# CR78-TB.net
KiCad netlist of a schematic drawn in EAGLE
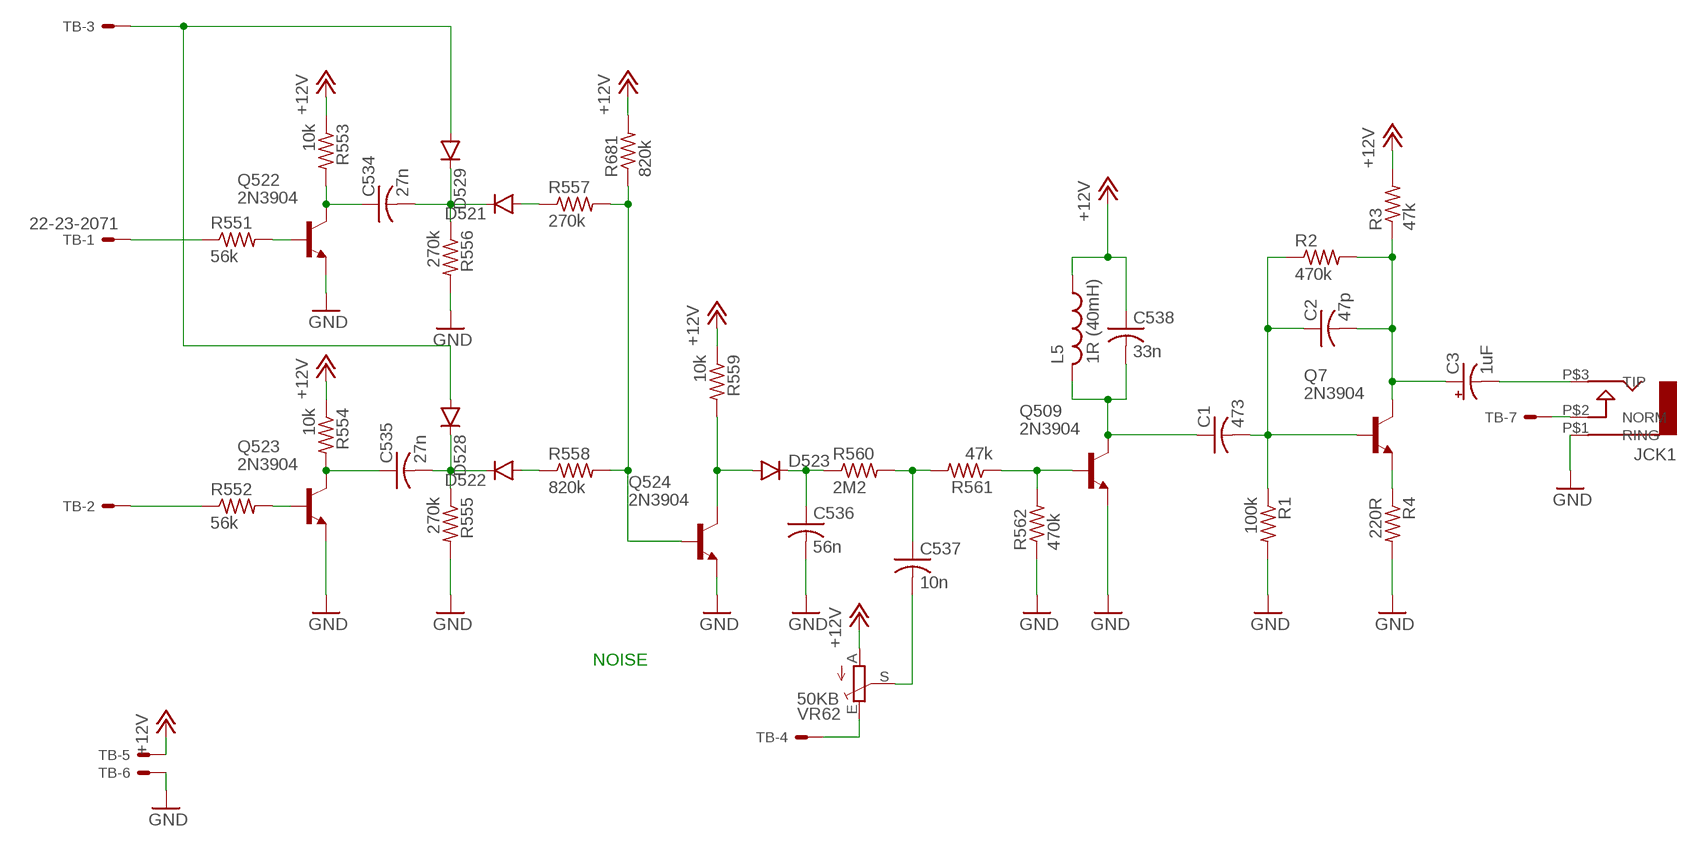
[diagram p0: schematic, sheet 1]

(export (version "E")
  (design (tool "Eeschema 10.0.6"))
  (components
    (comp (ref "C1")
      (value "473")
      (footprint "eagle-import:C050-025X075")
      (libsource (lib "eagle-import") (part "C-US050-025X075"))
    )
    (comp (ref "C2")
      (value "47p")
      (footprint "eagle-import:C050-025X075")
      (libsource (lib "eagle-import") (part "C-US050-025X075"))
    )
    (comp (ref "C3")
      (value "1uF")
      (footprint "eagle-import:B45181A")
      (libsource (lib "eagle-import") (part "CPOL-USB45181A"))
    )
    (comp (ref "C534")
      (value "27n")
      (footprint "eagle-import:C050-025X075")
      (libsource (lib "eagle-import") (part "C-US050-025X075"))
    )
    (comp (ref "C535")
      (value "27n")
      (footprint "eagle-import:C050-025X075")
      (libsource (lib "eagle-import") (part "C-US050-025X075"))
    )
    (comp (ref "C536")
      (value "56n")
      (footprint "eagle-import:C050-025X075")
      (libsource (lib "eagle-import") (part "C-US050-025X075"))
    )
    (comp (ref "C537")
      (value "10n")
      (footprint "eagle-import:C050-025X075")
      (libsource (lib "eagle-import") (part "C-US050-025X075"))
    )
    (comp (ref "C538")
      (value "33n")
      (footprint "eagle-import:C050-025X075")
      (libsource (lib "eagle-import") (part "C-US050-025X075"))
    )
    (comp (ref "D521")
      (value "DIODE1N4148")
      (footprint "eagle-import:DIODE-1N4148")
      (libsource (lib "eagle-import") (part "DIODE1N4148"))
    )
    (comp (ref "D522")
      (value "DIODE1N4148")
      (footprint "eagle-import:DIODE-1N4148")
      (libsource (lib "eagle-import") (part "DIODE1N4148"))
    )
    (comp (ref "D523")
      (value "DIODE1N4148")
      (footprint "eagle-import:DIODE-1N4148")
      (libsource (lib "eagle-import") (part "DIODE1N4148"))
    )
    (comp (ref "D528")
      (value "DIODE1N4148")
      (footprint "eagle-import:DIODE-1N4148")
      (libsource (lib "eagle-import") (part "DIODE1N4148"))
    )
    (comp (ref "D529")
      (value "DIODE1N4148")
      (footprint "eagle-import:DIODE-1N4148")
      (libsource (lib "eagle-import") (part "DIODE1N4148"))
    )
    (comp (ref "JCK1")
      (value "AUDIO-JACK")
      (footprint "eagle-import:ERTHENVAR-JACK-90DEG")
      (libsource (lib "eagle-import") (part "AUDIO-JACK"))
    )
    (comp (ref "L5")
      (value "1R (40mH)")
      (footprint "eagle-import:0207_5V")
      (libsource (lib "eagle-import") (part "L-US0207/5V"))
    )
    (comp (ref "Q7")
      (value "2N3904")
      (footprint "eagle-import:TO92")
      (libsource (lib "eagle-import") (part "2N3904"))
    )
    (comp (ref "Q509")
      (value "2N3904")
      (footprint "eagle-import:TO92")
      (libsource (lib "eagle-import") (part "2N3904"))
    )
    (comp (ref "Q522")
      (value "2N3904")
      (footprint "eagle-import:TO92")
      (libsource (lib "eagle-import") (part "2N3904"))
    )
    (comp (ref "Q523")
      (value "2N3904")
      (footprint "eagle-import:TO92")
      (libsource (lib "eagle-import") (part "2N3904"))
    )
    (comp (ref "Q524")
      (value "2N3904")
      (footprint "eagle-import:TO92")
      (libsource (lib "eagle-import") (part "2N3904"))
    )
    (comp (ref "R1")
      (value "100k")
      (footprint "eagle-import:0207_7")
      (libsource (lib "eagle-import") (part "R-US_0207/7"))
    )
    (comp (ref "R2")
      (value "470k")
      (footprint "eagle-import:0207_7")
      (libsource (lib "eagle-import") (part "R-US_0207/7"))
    )
    (comp (ref "R3")
      (value "47k")
      (footprint "eagle-import:0207_7")
      (libsource (lib "eagle-import") (part "R-US_0207/7"))
    )
    (comp (ref "R4")
      (value "220R")
      (footprint "eagle-import:0207_7")
      (libsource (lib "eagle-import") (part "R-US_0207/7"))
    )
    (comp (ref "R551")
      (value "56k")
      (footprint "eagle-import:0207_5V")
      (libsource (lib "eagle-import") (part "R-US_0207/5V"))
    )
    (comp (ref "R552")
      (value "56k")
      (footprint "eagle-import:0207_5V")
      (libsource (lib "eagle-import") (part "R-US_0207/5V"))
    )
    (comp (ref "R553")
      (value "10k")
      (footprint "eagle-import:0207_7")
      (libsource (lib "eagle-import") (part "R-US_0207/7"))
    )
    (comp (ref "R554")
      (value "10k")
      (footprint "eagle-import:0207_10")
      (libsource (lib "eagle-import") (part "R-US_0207/10"))
    )
    (comp (ref "R555")
      (value "270k")
      (footprint "eagle-import:0207_7")
      (libsource (lib "eagle-import") (part "R-US_0207/7"))
    )
    (comp (ref "R556")
      (value "270k")
      (footprint "eagle-import:0207_7")
      (libsource (lib "eagle-import") (part "R-US_0207/7"))
    )
    (comp (ref "R557")
      (value "270k")
      (footprint "eagle-import:0207_7")
      (libsource (lib "eagle-import") (part "R-US_0207/7"))
    )
    (comp (ref "R558")
      (value "820k")
      (footprint "eagle-import:0207_7")
      (libsource (lib "eagle-import") (part "R-US_0207/7"))
    )
    (comp (ref "R559")
      (value "10k")
      (footprint "eagle-import:0207_7")
      (libsource (lib "eagle-import") (part "R-US_0207/7"))
    )
    (comp (ref "R560")
      (value "2M2")
      (footprint "eagle-import:0207_7")
      (libsource (lib "eagle-import") (part "R-US_0207/7"))
    )
    (comp (ref "R561")
      (value "47k")
      (footprint "eagle-import:0207_7")
      (libsource (lib "eagle-import") (part "R-US_0207/7"))
    )
    (comp (ref "R562")
      (value "470k")
      (footprint "eagle-import:0207_7")
      (libsource (lib "eagle-import") (part "R-US_0207/7"))
    )
    (comp (ref "R681")
      (value "820k")
      (footprint "eagle-import:0207_7")
      (libsource (lib "eagle-import") (part "R-US_0207/7"))
    )
    (comp (ref "TB")
      (value "22-23-2071")
      (footprint "eagle-import:22-23-2071")
      (fields (field (name "MF") "MOLEX"))
      (libsource (lib "eagle-import") (part "22-23-2071"))
    )
    (comp (ref "VR62")
      (value "50KB")
      (footprint "eagle-import:B64Y")
      (libsource (lib "eagle-import") (part "TRIM_EU-B64Y"))
    )
  )
  (nets
    (net (code "1") (name "+12V") (class "Default")
      (node (ref "C538") (pin "1") (pinfunction "1_1") (pintype "passive"))
      (node (ref "L5") (pin "1") (pinfunction "1_1") (pintype "passive"))
      (node (ref "R3") (pin "2") (pinfunction "2_2") (pintype "passive"))
      (node (ref "R553") (pin "1") (pinfunction "1_1") (pintype "passive"))
      (node (ref "R554") (pin "1") (pinfunction "1_1") (pintype "passive"))
      (node (ref "R559") (pin "1") (pinfunction "1_1") (pintype "passive"))
      (node (ref "R681") (pin "2") (pinfunction "2_2") (pintype "passive"))
      (node (ref "TB") (pin "5") (pinfunction "S_5") (pintype "passive"))
      (node (ref "VR62") (pin "A") (pinfunction "A_A") (pintype "passive"))
    )
    (net (code "2") (name "GND") (class "Default")
      (node (ref "C536") (pin "2") (pinfunction "2_2") (pintype "passive"))
      (node (ref "JCK1") (pin "P$1") (pinfunction "RING_P$1") (pintype "bidirectional"))
      (node (ref "Q509") (pin "3") (pinfunction "E_3") (pintype "passive"))
      (node (ref "Q522") (pin "3") (pinfunction "E_3") (pintype "passive"))
      (node (ref "Q523") (pin "3") (pinfunction "E_3") (pintype "passive"))
      (node (ref "Q524") (pin "3") (pinfunction "E_3") (pintype "passive"))
      (node (ref "R1") (pin "2") (pinfunction "2_2") (pintype "passive"))
      (node (ref "R4") (pin "2") (pinfunction "2_2") (pintype "passive"))
      (node (ref "R555") (pin "2") (pinfunction "2_2") (pintype "passive"))
      (node (ref "R556") (pin "2") (pinfunction "2_2") (pintype "passive"))
      (node (ref "R562") (pin "1") (pinfunction "1_1") (pintype "passive"))
      (node (ref "TB") (pin "6") (pinfunction "S_6") (pintype "passive"))
    )
    (net (code "3") (name "Net-(C534-Pad2)") (class "Default")
      (node (ref "C534") (pin "2") (pinfunction "2_2") (pintype "passive"))
      (node (ref "D521") (pin "C") (pinfunction "C_C") (pintype "passive"))
      (node (ref "D529") (pin "C") (pinfunction "C_C") (pintype "passive"))
      (node (ref "R556") (pin "1") (pinfunction "1_1") (pintype "passive"))
    )
    (net (code "4") (name "Net-(C535-Pad2)") (class "Default")
      (node (ref "C535") (pin "2") (pinfunction "2_2") (pintype "passive"))
      (node (ref "D522") (pin "C") (pinfunction "C_C") (pintype "passive"))
      (node (ref "D528") (pin "C") (pinfunction "C_C") (pintype "passive"))
      (node (ref "R555") (pin "1") (pinfunction "1_1") (pintype "passive"))
    )
    (net (code "5") (name "Net-(C536-Pad1)") (class "Default")
      (node (ref "C536") (pin "1") (pinfunction "1_1") (pintype "passive"))
      (node (ref "D523") (pin "C") (pinfunction "C_C") (pintype "passive"))
      (node (ref "R560") (pin "1") (pinfunction "1_1") (pintype "passive"))
    )
    (net (code "6") (name "Net-(C537-Pad1)") (class "Default")
      (node (ref "C537") (pin "1") (pinfunction "1_1") (pintype "passive"))
      (node (ref "R560") (pin "2") (pinfunction "2_2") (pintype "passive"))
      (node (ref "R561") (pin "2") (pinfunction "2_2") (pintype "passive"))
    )
    (net (code "7") (name "Net-(C537-Pad2)") (class "Default")
      (node (ref "C537") (pin "2") (pinfunction "2_2") (pintype "passive"))
      (node (ref "VR62") (pin "S") (pinfunction "S_S") (pintype "passive"))
    )
    (net (code "8") (name "Net-(D521-PadA)") (class "Default")
      (node (ref "D521") (pin "A") (pinfunction "A_A") (pintype "passive"))
      (node (ref "R557") (pin "1") (pinfunction "1_1") (pintype "passive"))
    )
    (net (code "9") (name "Net-(D522-PadA)") (class "Default")
      (node (ref "D522") (pin "A") (pinfunction "A_A") (pintype "passive"))
      (node (ref "R558") (pin "1") (pinfunction "1_1") (pintype "passive"))
    )
    (net (code "10") (name "Net-(JCK1-NORM)") (class "Default")
      (node (ref "JCK1") (pin "P$2") (pinfunction "NORM_P$2") (pintype "bidirectional"))
      (node (ref "TB") (pin "7") (pinfunction "S_7") (pintype "passive"))
    )
    (net (code "11") (name "Net-(JCK1-TIP)") (class "Default")
      (node (ref "C3") (pin "-") (pinfunction "-_-") (pintype "passive"))
      (node (ref "JCK1") (pin "P$3") (pinfunction "TIP_P$3") (pintype "bidirectional"))
    )
    (net (code "12") (name "Net-(Q7-B)") (class "Default")
      (node (ref "C1") (pin "2") (pinfunction "2_2") (pintype "passive"))
      (node (ref "C2") (pin "1") (pinfunction "1_1") (pintype "passive"))
      (node (ref "Q7") (pin "2") (pinfunction "B_2") (pintype "passive"))
      (node (ref "R1") (pin "1") (pinfunction "1_1") (pintype "passive"))
      (node (ref "R2") (pin "1") (pinfunction "1_1") (pintype "passive"))
    )
    (net (code "13") (name "Net-(Q7-C)") (class "Default")
      (node (ref "C2") (pin "2") (pinfunction "2_2") (pintype "passive"))
      (node (ref "C3") (pin "+") (pinfunction "+_+") (pintype "passive"))
      (node (ref "Q7") (pin "1") (pinfunction "C_1") (pintype "passive"))
      (node (ref "R2") (pin "2") (pinfunction "2_2") (pintype "passive"))
      (node (ref "R3") (pin "1") (pinfunction "1_1") (pintype "passive"))
    )
    (net (code "14") (name "Net-(Q7-E)") (class "Default")
      (node (ref "Q7") (pin "3") (pinfunction "E_3") (pintype "passive"))
      (node (ref "R4") (pin "1") (pinfunction "1_1") (pintype "passive"))
    )
    (net (code "15") (name "Net-(Q509-B)") (class "Default")
      (node (ref "Q509") (pin "2") (pinfunction "B_2") (pintype "passive"))
      (node (ref "R561") (pin "1") (pinfunction "1_1") (pintype "passive"))
      (node (ref "R562") (pin "2") (pinfunction "2_2") (pintype "passive"))
    )
    (net (code "16") (name "Net-(Q509-C)") (class "Default")
      (node (ref "C1") (pin "1") (pinfunction "1_1") (pintype "passive"))
      (node (ref "C538") (pin "2") (pinfunction "2_2") (pintype "passive"))
      (node (ref "L5") (pin "2") (pinfunction "2_2") (pintype "passive"))
      (node (ref "Q509") (pin "1") (pinfunction "C_1") (pintype "passive"))
    )
    (net (code "17") (name "Net-(Q522-B)") (class "Default")
      (node (ref "Q522") (pin "2") (pinfunction "B_2") (pintype "passive"))
      (node (ref "R551") (pin "2") (pinfunction "2_2") (pintype "passive"))
    )
    (net (code "18") (name "Net-(Q522-C)") (class "Default")
      (node (ref "C534") (pin "1") (pinfunction "1_1") (pintype "passive"))
      (node (ref "Q522") (pin "1") (pinfunction "C_1") (pintype "passive"))
      (node (ref "R553") (pin "2") (pinfunction "2_2") (pintype "passive"))
    )
    (net (code "19") (name "Net-(Q523-B)") (class "Default")
      (node (ref "Q523") (pin "2") (pinfunction "B_2") (pintype "passive"))
      (node (ref "R552") (pin "2") (pinfunction "2_2") (pintype "passive"))
    )
    (net (code "20") (name "Net-(Q523-C)") (class "Default")
      (node (ref "C535") (pin "1") (pinfunction "1_1") (pintype "passive"))
      (node (ref "Q523") (pin "1") (pinfunction "C_1") (pintype "passive"))
      (node (ref "R554") (pin "2") (pinfunction "2_2") (pintype "passive"))
    )
    (net (code "21") (name "Net-(Q524-B)") (class "Default")
      (node (ref "Q524") (pin "2") (pinfunction "B_2") (pintype "passive"))
      (node (ref "R557") (pin "2") (pinfunction "2_2") (pintype "passive"))
      (node (ref "R558") (pin "2") (pinfunction "2_2") (pintype "passive"))
      (node (ref "R681") (pin "1") (pinfunction "1_1") (pintype "passive"))
    )
    (net (code "22") (name "Net-(Q524-C)") (class "Default")
      (node (ref "D523") (pin "A") (pinfunction "A_A") (pintype "passive"))
      (node (ref "Q524") (pin "1") (pinfunction "C_1") (pintype "passive"))
      (node (ref "R559") (pin "2") (pinfunction "2_2") (pintype "passive"))
    )
    (net (code "23") (name "Net-(TBA-S)") (class "Default")
      (node (ref "R551") (pin "1") (pinfunction "1_1") (pintype "passive"))
      (node (ref "TB") (pin "1") (pinfunction "S_1") (pintype "passive"))
    )
    (net (code "24") (name "Net-(TBB-S)") (class "Default")
      (node (ref "R552") (pin "1") (pinfunction "1_1") (pintype "passive"))
      (node (ref "TB") (pin "2") (pinfunction "S_2") (pintype "passive"))
    )
    (net (code "25") (name "Net-(TBC-S)") (class "Default")
      (node (ref "D528") (pin "A") (pinfunction "A_A") (pintype "passive"))
      (node (ref "D529") (pin "A") (pinfunction "A_A") (pintype "passive"))
      (node (ref "TB") (pin "3") (pinfunction "S_3") (pintype "passive"))
    )
    (net (code "26") (name "Net-(TBD-S)") (class "Default")
      (node (ref "TB") (pin "4") (pinfunction "S_4") (pintype "passive"))
      (node (ref "VR62") (pin "E") (pinfunction "E_E") (pintype "passive"))
    )
  )
)
